# untitled.net
KiCad netlist of a schematic drawn in EAGLE
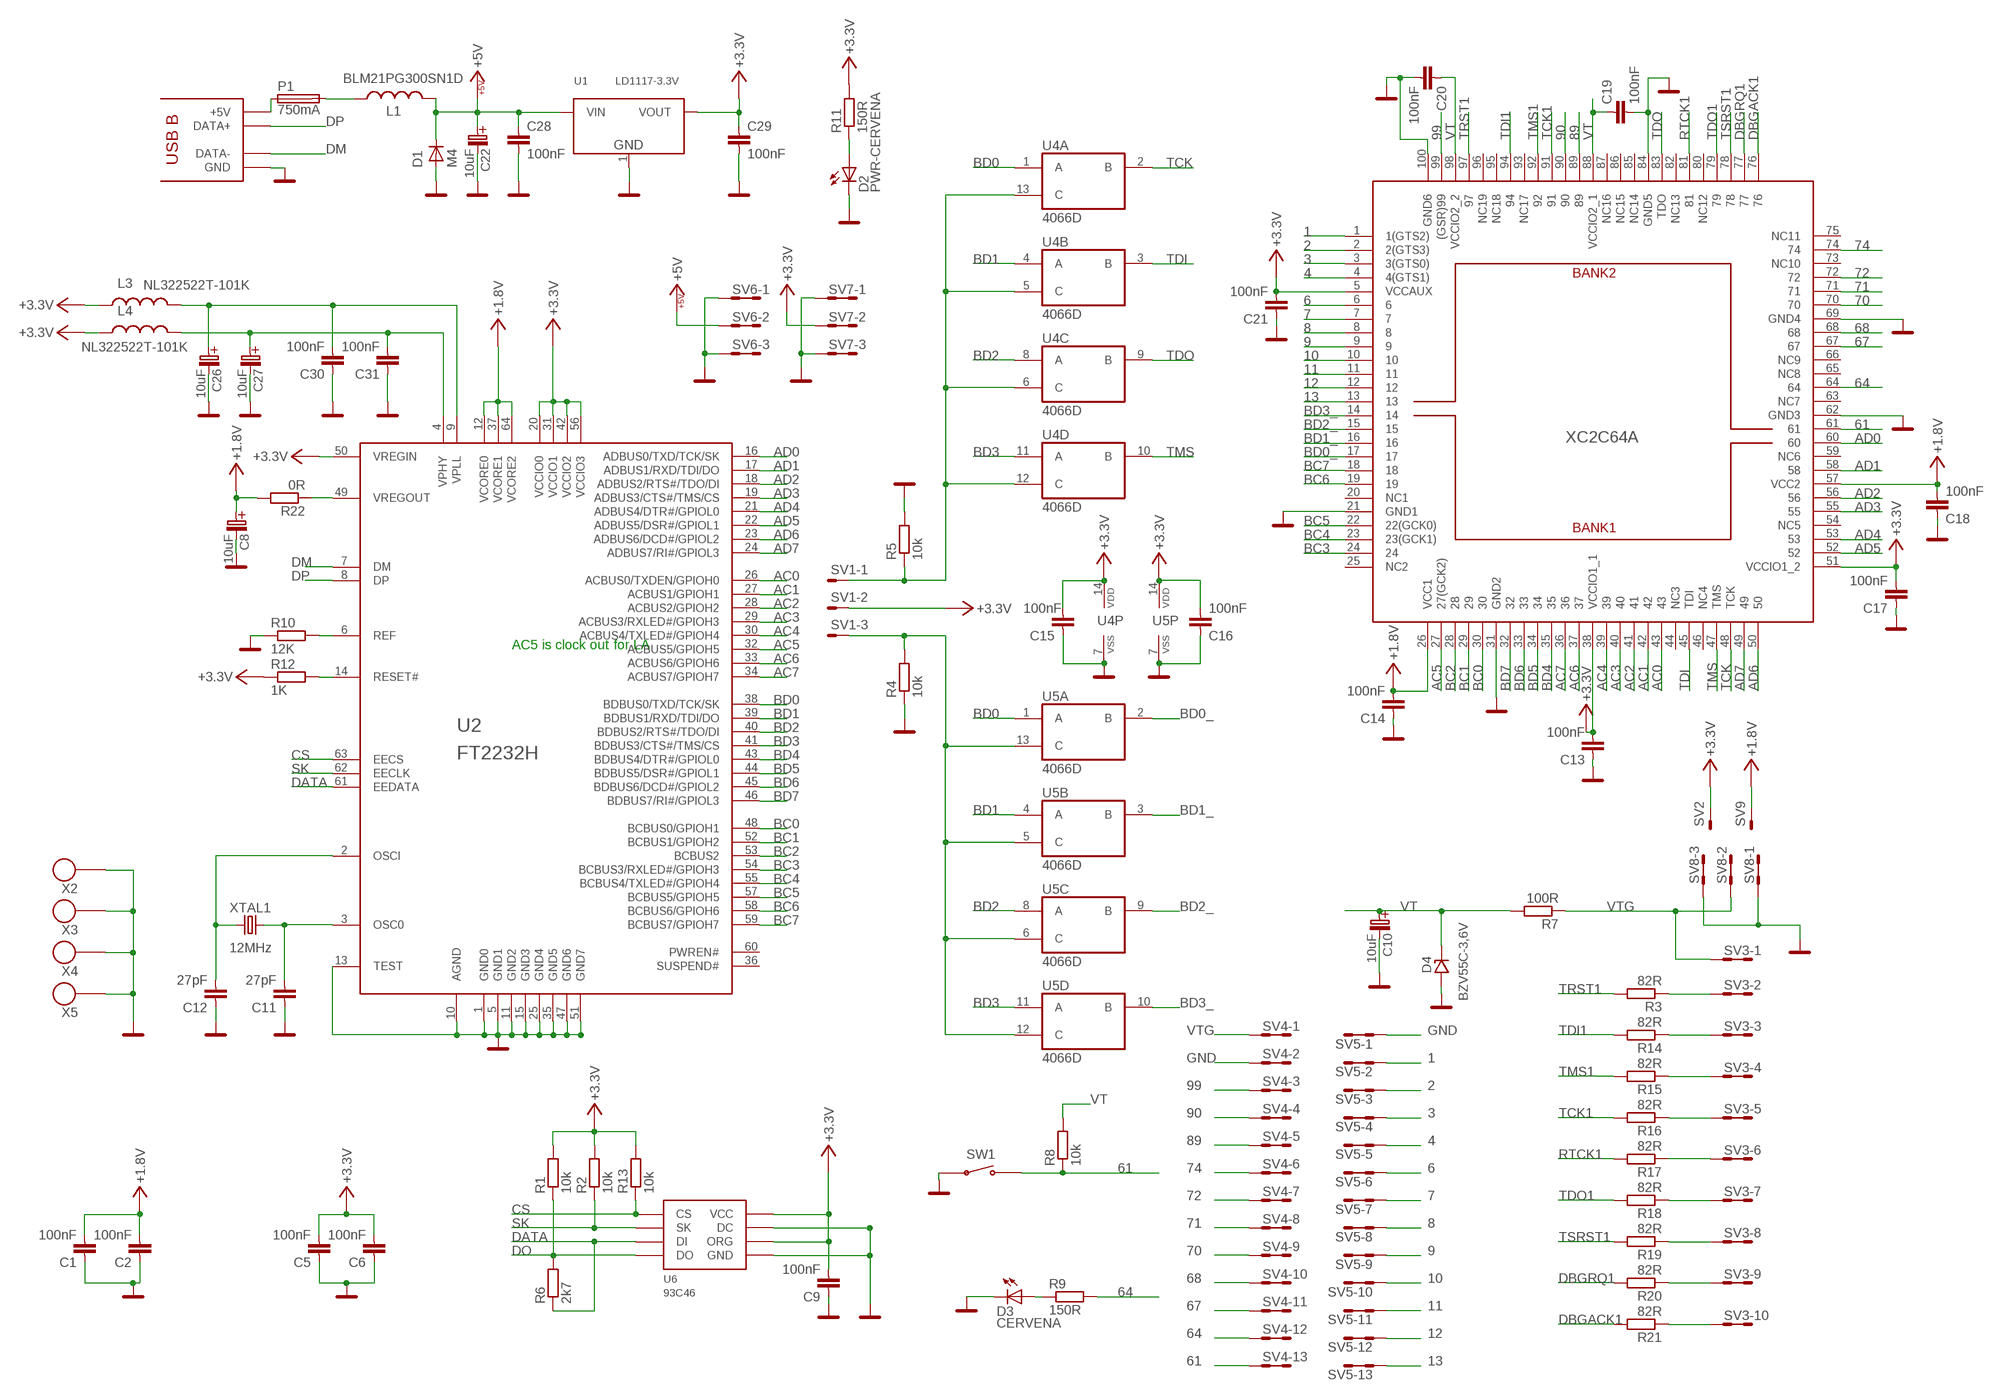
[diagram p0: schematic, sheet 1]

(export (version "E")
  (design (tool "Eeschema 10.0.6"))
  (components
    (comp (ref "C1")
      (value "100nF")
      (footprint "eagle-import:C0805")
      (libsource (lib "eagle-import") (part "C0805"))
    )
    (comp (ref "C2")
      (value "100nF")
      (footprint "eagle-import:C0805")
      (libsource (lib "eagle-import") (part "C0805"))
    )
    (comp (ref "C5")
      (value "100nF")
      (footprint "eagle-import:C0805")
      (libsource (lib "eagle-import") (part "C0805"))
    )
    (comp (ref "C6")
      (value "100nF")
      (footprint "eagle-import:C0805")
      (libsource (lib "eagle-import") (part "C0805"))
    )
    (comp (ref "C8") (value "10uF") (footprint "eagle-import:B") (libsource (lib "eagle-import") (part "B")))
    (comp (ref "C9")
      (value "100nF")
      (footprint "eagle-import:C0805")
      (libsource (lib "eagle-import") (part "C0805"))
    )
    (comp (ref "C10") (value "10uF") (footprint "eagle-import:B") (libsource (lib "eagle-import") (part "B")))
    (comp (ref "C11")
      (value "27pF")
      (footprint "eagle-import:C0805")
      (libsource (lib "eagle-import") (part "C0805"))
    )
    (comp (ref "C12")
      (value "27pF")
      (footprint "eagle-import:C0805")
      (libsource (lib "eagle-import") (part "C0805"))
    )
    (comp (ref "C13")
      (value "100nF")
      (footprint "eagle-import:C0805")
      (libsource (lib "eagle-import") (part "C0805"))
    )
    (comp (ref "C14")
      (value "100nF")
      (footprint "eagle-import:C0805")
      (libsource (lib "eagle-import") (part "C0805"))
    )
    (comp (ref "C15")
      (value "100nF")
      (footprint "eagle-import:C0805")
      (libsource (lib "eagle-import") (part "C0805"))
    )
    (comp (ref "C16")
      (value "100nF")
      (footprint "eagle-import:C0805")
      (libsource (lib "eagle-import") (part "C0805"))
    )
    (comp (ref "C17")
      (value "100nF")
      (footprint "eagle-import:C0805")
      (libsource (lib "eagle-import") (part "C0805"))
    )
    (comp (ref "C18")
      (value "100nF")
      (footprint "eagle-import:C0805")
      (libsource (lib "eagle-import") (part "C0805"))
    )
    (comp (ref "C19")
      (value "100nF")
      (footprint "eagle-import:C0805")
      (libsource (lib "eagle-import") (part "C0805"))
    )
    (comp (ref "C20")
      (value "100nF")
      (footprint "eagle-import:C0805")
      (libsource (lib "eagle-import") (part "C0805"))
    )
    (comp (ref "C21")
      (value "100nF")
      (footprint "eagle-import:C0805")
      (libsource (lib "eagle-import") (part "C0805"))
    )
    (comp (ref "C22") (value "10uF") (footprint "eagle-import:B") (libsource (lib "eagle-import") (part "B")))
    (comp (ref "C26") (value "10uF") (footprint "eagle-import:B") (libsource (lib "eagle-import") (part "B")))
    (comp (ref "C27") (value "10uF") (footprint "eagle-import:B") (libsource (lib "eagle-import") (part "B")))
    (comp (ref "C28")
      (value "100nF")
      (footprint "eagle-import:C0805")
      (libsource (lib "eagle-import") (part "C0805"))
    )
    (comp (ref "C29")
      (value "100nF")
      (footprint "eagle-import:C0805")
      (libsource (lib "eagle-import") (part "C0805"))
    )
    (comp (ref "C30")
      (value "100nF")
      (footprint "eagle-import:C0805")
      (libsource (lib "eagle-import") (part "C0805"))
    )
    (comp (ref "C31")
      (value "100nF")
      (footprint "eagle-import:C0805")
      (libsource (lib "eagle-import") (part "C0805"))
    )
    (comp (ref "D1")
      (value "M4")
      (footprint "eagle-import:SMA")
      (libsource (lib "eagle-import") (part "D-OB.SMA"))
    )
    (comp (ref "D2")
      (value "PWR-CERVENA")
      (footprint "eagle-import:1206")
      (libsource (lib "eagle-import") (part "LED1206"))
    )
    (comp (ref "D3")
      (value "CERVENA")
      (footprint "eagle-import:1206")
      (libsource (lib "eagle-import") (part "LED1206"))
    )
    (comp (ref "D4")
      (value "BZV55C-3,6V")
      (footprint "eagle-import:MINIMELF")
      (libsource (lib "eagle-import") (part "D-ZENEROVA"))
    )
    (comp (ref "L1")
      (value "BLM21PG300SN1D")
      (footprint "eagle-import:L0805")
      (libsource (lib "eagle-import") (part "L0805"))
    )
    (comp (ref "L3")
      (value "NL322522T-101K")
      (footprint "eagle-import:1210")
      (libsource (lib "eagle-import") (part "L1210"))
    )
    (comp (ref "L4")
      (value "NL322522T-101K")
      (footprint "eagle-import:1210")
      (libsource (lib "eagle-import") (part "L1210"))
    )
    (comp (ref "P1")
      (value "750mA")
      (footprint "eagle-import:1812")
      (libsource (lib "eagle-import") (part "POJISTKA_1812"))
    )
    (comp (ref "R1")
      (value "10k")
      (footprint "eagle-import:0805")
      (libsource (lib "eagle-import") (part "R0805"))
    )
    (comp (ref "R2")
      (value "10k")
      (footprint "eagle-import:0805")
      (libsource (lib "eagle-import") (part "R0805"))
    )
    (comp (ref "R3")
      (value "82R")
      (footprint "eagle-import:0805")
      (libsource (lib "eagle-import") (part "R0805"))
    )
    (comp (ref "R4")
      (value "10k")
      (footprint "eagle-import:0805")
      (libsource (lib "eagle-import") (part "R0805"))
    )
    (comp (ref "R5")
      (value "10k")
      (footprint "eagle-import:0805")
      (libsource (lib "eagle-import") (part "R0805"))
    )
    (comp (ref "R6")
      (value "2k7")
      (footprint "eagle-import:0805")
      (libsource (lib "eagle-import") (part "R0805"))
    )
    (comp (ref "R7")
      (value "100R")
      (footprint "eagle-import:0805")
      (libsource (lib "eagle-import") (part "R0805"))
    )
    (comp (ref "R8")
      (value "10k")
      (footprint "eagle-import:0805")
      (libsource (lib "eagle-import") (part "R0805"))
    )
    (comp (ref "R9")
      (value "150R")
      (footprint "eagle-import:0805")
      (libsource (lib "eagle-import") (part "R0805"))
    )
    (comp (ref "R10")
      (value "12K")
      (footprint "eagle-import:0805")
      (libsource (lib "eagle-import") (part "R0805"))
    )
    (comp (ref "R11")
      (value "150R")
      (footprint "eagle-import:0805")
      (libsource (lib "eagle-import") (part "R0805"))
    )
    (comp (ref "R12")
      (value "1K")
      (footprint "eagle-import:0805")
      (libsource (lib "eagle-import") (part "R0805"))
    )
    (comp (ref "R13")
      (value "10k")
      (footprint "eagle-import:0805")
      (libsource (lib "eagle-import") (part "R0805"))
    )
    (comp (ref "R14")
      (value "82R")
      (footprint "eagle-import:0805")
      (libsource (lib "eagle-import") (part "R0805"))
    )
    (comp (ref "R15")
      (value "82R")
      (footprint "eagle-import:0805")
      (libsource (lib "eagle-import") (part "R0805"))
    )
    (comp (ref "R16")
      (value "82R")
      (footprint "eagle-import:0805")
      (libsource (lib "eagle-import") (part "R0805"))
    )
    (comp (ref "R17")
      (value "82R")
      (footprint "eagle-import:0805")
      (libsource (lib "eagle-import") (part "R0805"))
    )
    (comp (ref "R18")
      (value "82R")
      (footprint "eagle-import:0805")
      (libsource (lib "eagle-import") (part "R0805"))
    )
    (comp (ref "R19")
      (value "82R")
      (footprint "eagle-import:0805")
      (libsource (lib "eagle-import") (part "R0805"))
    )
    (comp (ref "R20")
      (value "82R")
      (footprint "eagle-import:0805")
      (libsource (lib "eagle-import") (part "R0805"))
    )
    (comp (ref "R21")
      (value "82R")
      (footprint "eagle-import:0805")
      (libsource (lib "eagle-import") (part "R0805"))
    )
    (comp (ref "R22")
      (value "0R")
      (footprint "eagle-import:0805")
      (libsource (lib "eagle-import") (part "R0805"))
    )
    (comp (ref "SV1")
      (value "MA03-1")
      (footprint "eagle-import:MA03-1")
      (libsource (lib "eagle-import") (part "MA03-1"))
    )
    (comp (ref "SV2")
      (value "MA01-1")
      (footprint "eagle-import:MA01-1")
      (libsource (lib "eagle-import") (part "MA01-1"))
    )
    (comp (ref "SV3")
      (value "MA10-2")
      (footprint "eagle-import:MA10-2")
      (libsource (lib "eagle-import") (part "MA10-2"))
    )
    (comp (ref "SV4")
      (value "MA13-2")
      (footprint "eagle-import:MA13-2")
      (libsource (lib "eagle-import") (part "MA13-2"))
    )
    (comp (ref "SV5")
      (value "MA13-2")
      (footprint "eagle-import:MA13-2")
      (libsource (lib "eagle-import") (part "MA13-2"))
    )
    (comp (ref "SV6")
      (value "MA03-2")
      (footprint "eagle-import:MA03-2")
      (libsource (lib "eagle-import") (part "MA03-2"))
    )
    (comp (ref "SV7")
      (value "MA03-2")
      (footprint "eagle-import:MA03-2")
      (libsource (lib "eagle-import") (part "MA03-2"))
    )
    (comp (ref "SV8")
      (value "MA03-2")
      (footprint "eagle-import:MA03-2")
      (libsource (lib "eagle-import") (part "MA03-2"))
    )
    (comp (ref "SV9")
      (value "MA01-1")
      (footprint "eagle-import:MA01-1")
      (libsource (lib "eagle-import") (part "MA01-1"))
    )
    (comp (ref "SW1")
      (value "TACT-64K")
      (footprint "eagle-import:TACT-64K")
      (libsource (lib "eagle-import") (part "TACT-64K"))
    )
    (comp (ref "U1")
      (value "LD1117-3.3V")
      (footprint "eagle-import:SOT223")
      (libsource (lib "eagle-import") (part "LD1117-3.3SOT223"))
    )
    (comp (ref "U2")
      (value "FT2232H")
      (footprint "eagle-import:LQFP64")
      (libsource (lib "eagle-import") (part "FT2232H"))
    )
    (comp (ref "U3")
      (value "XC2C64A")
      (footprint "eagle-import:VQ100")
      (libsource (lib "eagle-import") (part "XC2C64A"))
    )
    (comp (ref "U4")
      (value "4066D")
      (footprint "eagle-import:SO14")
      (libsource (lib "eagle-import") (part "4066D"))
    )
    (comp (ref "U5")
      (value "4066D")
      (footprint "eagle-import:SO14")
      (libsource (lib "eagle-import") (part "4066D"))
    )
    (comp (ref "U6")
      (value "93C46")
      (footprint "eagle-import:SOIC8")
      (libsource (lib "eagle-import") (part "93C46"))
    )
    (comp (ref "X1")
      (value "USB_B")
      (footprint "eagle-import:USB_B")
      (libsource (lib "eagle-import") (part "USB_B"))
    )
    (comp (ref "X2")
      (value "SROUB3M")
      (footprint "eagle-import:SROUB3M")
      (libsource (lib "eagle-import") (part "SROUB3M"))
    )
    (comp (ref "X3")
      (value "SROUB3M")
      (footprint "eagle-import:SROUB3M")
      (libsource (lib "eagle-import") (part "SROUB3M"))
    )
    (comp (ref "X4")
      (value "SROUB3M")
      (footprint "eagle-import:SROUB3M")
      (libsource (lib "eagle-import") (part "SROUB3M"))
    )
    (comp (ref "X5")
      (value "SROUB3M")
      (footprint "eagle-import:SROUB3M")
      (libsource (lib "eagle-import") (part "SROUB3M"))
    )
    (comp (ref "XTAL1")
      (value "12MHz")
      (footprint "eagle-import:S49")
      (libsource (lib "eagle-import") (part "KRYSLAL_S49"))
    )
  )
  (nets
    (net (code "1") (name "+1.8V") (class "Default")
      (node (ref "C1") (pin "2") (pinfunction "2_2") (pintype "passive"))
      (node (ref "C14") (pin "2") (pinfunction "2_2") (pintype "passive"))
      (node (ref "C18") (pin "2") (pinfunction "2_2") (pintype "passive"))
      (node (ref "C2") (pin "2") (pinfunction "2_2") (pintype "passive"))
      (node (ref "C8") (pin "+") (pinfunction "C_EL+_+") (pintype "passive"))
      (node (ref "R22") (pin "2") (pinfunction "2_2") (pintype "passive"))
      (node (ref "SV9") (pin "1") (pinfunction "P$1_1") (pintype "passive"))
      (node (ref "U2") (pin "12") (pinfunction "VCORE0_12") (pintype "bidirectional"))
      (node (ref "U2") (pin "37") (pinfunction "VCORE1_37") (pintype "bidirectional"))
      (node (ref "U2") (pin "64") (pinfunction "VCORE2_64") (pintype "bidirectional"))
      (node (ref "U3") (pin "26") (pinfunction "VCC1_26") (pintype "bidirectional"))
      (node (ref "U3") (pin "57") (pinfunction "VCC2_57") (pintype "bidirectional"))
    )
    (net (code "2") (name "+3.3V") (class "Default")
      (node (ref "C13") (pin "2") (pinfunction "2_2") (pintype "passive"))
      (node (ref "C15") (pin "2") (pinfunction "2_2") (pintype "passive"))
      (node (ref "C16") (pin "2") (pinfunction "2_2") (pintype "passive"))
      (node (ref "C17") (pin "2") (pinfunction "2_2") (pintype "passive"))
      (node (ref "C21") (pin "2") (pinfunction "2_2") (pintype "passive"))
      (node (ref "C29") (pin "1") (pinfunction "1_1") (pintype "passive"))
      (node (ref "C5") (pin "2") (pinfunction "2_2") (pintype "passive"))
      (node (ref "C6") (pin "2") (pinfunction "2_2") (pintype "passive"))
      (node (ref "C9") (pin "2") (pinfunction "2_2") (pintype "passive"))
      (node (ref "L3") (pin "P$1") (pinfunction "1_P$1") (pintype "passive"))
      (node (ref "L4") (pin "P$1") (pinfunction "1_P$1") (pintype "passive"))
      (node (ref "R1") (pin "2") (pinfunction "2_2") (pintype "passive"))
      (node (ref "R11") (pin "2") (pinfunction "2_2") (pintype "passive"))
      (node (ref "R12") (pin "1") (pinfunction "1_1") (pintype "passive"))
      (node (ref "R13") (pin "2") (pinfunction "2_2") (pintype "passive"))
      (node (ref "R2") (pin "2") (pinfunction "2_2") (pintype "passive"))
      (node (ref "SV1") (pin "2") (pinfunction "P$1_2") (pintype "passive"))
      (node (ref "SV2") (pin "1") (pinfunction "P$1_1") (pintype "passive"))
      (node (ref "SV7") (pin "3") (pinfunction "K_3") (pintype "passive"))
      (node (ref "SV7") (pin "4") (pinfunction "K_4") (pintype "passive"))
      (node (ref "U1") (pin "2") (pinfunction "VOUT_2") (pintype "bidirectional"))
      (node (ref "U2") (pin "20") (pinfunction "VCCIO0_20") (pintype "bidirectional"))
      (node (ref "U2") (pin "31") (pinfunction "VCCIO1_31") (pintype "bidirectional"))
      (node (ref "U2") (pin "42") (pinfunction "VCCIO2_42") (pintype "bidirectional"))
      (node (ref "U2") (pin "50") (pinfunction "VREGIN_50") (pintype "bidirectional"))
      (node (ref "U2") (pin "56") (pinfunction "VCCIO3_56") (pintype "bidirectional"))
      (node (ref "U3") (pin "38") (pinfunction "VCCIO1_1_38") (pintype "bidirectional"))
      (node (ref "U3") (pin "5") (pinfunction "VCCAUX_5") (pintype "bidirectional"))
      (node (ref "U3") (pin "51") (pinfunction "VCCIO1_2_51") (pintype "bidirectional"))
      (node (ref "U4") (pin "14") (pinfunction "VDD_14") (pintype "power_in"))
      (node (ref "U5") (pin "14") (pinfunction "VDD_14") (pintype "power_in"))
      (node (ref "U6") (pin "6") (pinfunction "ORG_6") (pintype "bidirectional"))
      (node (ref "U6") (pin "8") (pinfunction "VCC_8") (pintype "bidirectional"))
    )
    (net (code "3") (name "+5V") (class "Default")
      (node (ref "C22") (pin "+") (pinfunction "C_EL+_+") (pintype "passive"))
      (node (ref "C28") (pin "1") (pinfunction "1_1") (pintype "passive"))
      (node (ref "D1") (pin "K") (pinfunction "C_K") (pintype "passive"))
      (node (ref "L1") (pin "2") (pinfunction "2_2") (pintype "passive"))
      (node (ref "SV6") (pin "3") (pinfunction "K_3") (pintype "passive"))
      (node (ref "SV6") (pin "4") (pinfunction "K_4") (pintype "passive"))
      (node (ref "U1") (pin "3") (pinfunction "VIN_3") (pintype "bidirectional"))
    )
    (net (code "4") (name "/1") (class "Default")
      (node (ref "SV5") (pin "3") (pinfunction "K_3") (pintype "passive"))
      (node (ref "SV5") (pin "4") (pinfunction "K_4") (pintype "passive"))
      (node (ref "U3") (pin "1") (pinfunction "1(GTS2)_1") (pintype "bidirectional"))
    )
    (net (code "5") (name "/2") (class "Default")
      (node (ref "SV5") (pin "5") (pinfunction "K_5") (pintype "passive"))
      (node (ref "SV5") (pin "6") (pinfunction "K_6") (pintype "passive"))
      (node (ref "U3") (pin "2") (pinfunction "2(GTS3)_2") (pintype "bidirectional"))
    )
    (net (code "6") (name "/3") (class "Default")
      (node (ref "SV5") (pin "7") (pinfunction "K_7") (pintype "passive"))
      (node (ref "SV5") (pin "8") (pinfunction "K_8") (pintype "passive"))
      (node (ref "U3") (pin "3") (pinfunction "3(GTS0)_3") (pintype "bidirectional"))
    )
    (net (code "7") (name "/4") (class "Default")
      (node (ref "SV5") (pin "10") (pinfunction "K_10") (pintype "passive"))
      (node (ref "SV5") (pin "9") (pinfunction "K_9") (pintype "passive"))
      (node (ref "U3") (pin "4") (pinfunction "4(GTS1)_4") (pintype "bidirectional"))
    )
    (net (code "8") (name "/6") (class "Default")
      (node (ref "SV5") (pin "11") (pinfunction "K_11") (pintype "passive"))
      (node (ref "SV5") (pin "12") (pinfunction "K_12") (pintype "passive"))
      (node (ref "U3") (pin "6") (pinfunction "6_6") (pintype "bidirectional"))
    )
    (net (code "9") (name "/7") (class "Default")
      (node (ref "SV5") (pin "13") (pinfunction "K_13") (pintype "passive"))
      (node (ref "SV5") (pin "14") (pinfunction "K_14") (pintype "passive"))
      (node (ref "U3") (pin "7") (pinfunction "7_7") (pintype "bidirectional"))
    )
    (net (code "10") (name "/8") (class "Default")
      (node (ref "SV5") (pin "15") (pinfunction "K_15") (pintype "passive"))
      (node (ref "SV5") (pin "16") (pinfunction "K_16") (pintype "passive"))
      (node (ref "U3") (pin "8") (pinfunction "8_8") (pintype "bidirectional"))
    )
    (net (code "11") (name "/9") (class "Default")
      (node (ref "SV5") (pin "17") (pinfunction "K_17") (pintype "passive"))
      (node (ref "SV5") (pin "18") (pinfunction "K_18") (pintype "passive"))
      (node (ref "U3") (pin "9") (pinfunction "9_9") (pintype "bidirectional"))
    )
    (net (code "12") (name "/10") (class "Default")
      (node (ref "SV5") (pin "19") (pinfunction "K_19") (pintype "passive"))
      (node (ref "SV5") (pin "20") (pinfunction "K_20") (pintype "passive"))
      (node (ref "U3") (pin "10") (pinfunction "10_10") (pintype "bidirectional"))
    )
    (net (code "13") (name "/11") (class "Default")
      (node (ref "SV5") (pin "21") (pinfunction "K_21") (pintype "passive"))
      (node (ref "SV5") (pin "22") (pinfunction "K_22") (pintype "passive"))
      (node (ref "U3") (pin "11") (pinfunction "11_11") (pintype "bidirectional"))
    )
    (net (code "14") (name "/12") (class "Default")
      (node (ref "SV5") (pin "23") (pinfunction "K_23") (pintype "passive"))
      (node (ref "SV5") (pin "24") (pinfunction "K_24") (pintype "passive"))
      (node (ref "U3") (pin "12") (pinfunction "12_12") (pintype "bidirectional"))
    )
    (net (code "15") (name "/13") (class "Default")
      (node (ref "SV5") (pin "25") (pinfunction "K_25") (pintype "passive"))
      (node (ref "SV5") (pin "26") (pinfunction "K_26") (pintype "passive"))
      (node (ref "U3") (pin "13") (pinfunction "13_13") (pintype "bidirectional"))
    )
    (net (code "16") (name "/61") (class "Default")
      (node (ref "R8") (pin "1") (pinfunction "1_1") (pintype "passive"))
      (node (ref "SV4") (pin "25") (pinfunction "K_25") (pintype "passive"))
      (node (ref "SV4") (pin "26") (pinfunction "K_26") (pintype "passive"))
      (node (ref "SW1") (pin "P$3") (pinfunction "P$2_P$3") (pintype "passive"))
      (node (ref "SW1") (pin "P$4") (pinfunction "P$2_P$4") (pintype "passive"))
      (node (ref "U3") (pin "61") (pinfunction "61_61") (pintype "bidirectional"))
    )
    (net (code "17") (name "/64") (class "Default")
      (node (ref "R9") (pin "2") (pinfunction "2_2") (pintype "passive"))
      (node (ref "SV4") (pin "23") (pinfunction "K_23") (pintype "passive"))
      (node (ref "SV4") (pin "24") (pinfunction "K_24") (pintype "passive"))
      (node (ref "U3") (pin "64") (pinfunction "64_64") (pintype "bidirectional"))
    )
    (net (code "18") (name "/67") (class "Default")
      (node (ref "SV4") (pin "21") (pinfunction "K_21") (pintype "passive"))
      (node (ref "SV4") (pin "22") (pinfunction "K_22") (pintype "passive"))
      (node (ref "U3") (pin "67") (pinfunction "67_67") (pintype "bidirectional"))
    )
    (net (code "19") (name "/68") (class "Default")
      (node (ref "SV4") (pin "19") (pinfunction "K_19") (pintype "passive"))
      (node (ref "SV4") (pin "20") (pinfunction "K_20") (pintype "passive"))
      (node (ref "U3") (pin "68") (pinfunction "68_68") (pintype "bidirectional"))
    )
    (net (code "20") (name "/70") (class "Default")
      (node (ref "SV4") (pin "17") (pinfunction "K_17") (pintype "passive"))
      (node (ref "SV4") (pin "18") (pinfunction "K_18") (pintype "passive"))
      (node (ref "U3") (pin "70") (pinfunction "70_70") (pintype "bidirectional"))
    )
    (net (code "21") (name "/71") (class "Default")
      (node (ref "SV4") (pin "15") (pinfunction "K_15") (pintype "passive"))
      (node (ref "SV4") (pin "16") (pinfunction "K_16") (pintype "passive"))
      (node (ref "U3") (pin "71") (pinfunction "71_71") (pintype "bidirectional"))
    )
    (net (code "22") (name "/72") (class "Default")
      (node (ref "SV4") (pin "13") (pinfunction "K_13") (pintype "passive"))
      (node (ref "SV4") (pin "14") (pinfunction "K_14") (pintype "passive"))
      (node (ref "U3") (pin "72") (pinfunction "72_72") (pintype "bidirectional"))
    )
    (net (code "23") (name "/74") (class "Default")
      (node (ref "SV4") (pin "11") (pinfunction "K_11") (pintype "passive"))
      (node (ref "SV4") (pin "12") (pinfunction "K_12") (pintype "passive"))
      (node (ref "U3") (pin "74") (pinfunction "74_74") (pintype "bidirectional"))
    )
    (net (code "24") (name "/89") (class "Default")
      (node (ref "SV4") (pin "10") (pinfunction "K_10") (pintype "passive"))
      (node (ref "SV4") (pin "9") (pinfunction "K_9") (pintype "passive"))
      (node (ref "U3") (pin "89") (pinfunction "89_89") (pintype "bidirectional"))
    )
    (net (code "25") (name "/90") (class "Default")
      (node (ref "SV4") (pin "7") (pinfunction "K_7") (pintype "passive"))
      (node (ref "SV4") (pin "8") (pinfunction "K_8") (pintype "passive"))
      (node (ref "U3") (pin "90") (pinfunction "90_90") (pintype "bidirectional"))
    )
    (net (code "26") (name "/99") (class "Default")
      (node (ref "SV4") (pin "5") (pinfunction "K_5") (pintype "passive"))
      (node (ref "SV4") (pin "6") (pinfunction "K_6") (pintype "passive"))
      (node (ref "U3") (pin "99") (pinfunction "(GSR)99_99") (pintype "bidirectional"))
    )
    (net (code "27") (name "/AC0") (class "Default")
      (node (ref "U2") (pin "26") (pinfunction "ACBUS0/TXDEN/GPIOH0_26") (pintype "bidirectional"))
      (node (ref "U3") (pin "43") (pinfunction "43_43") (pintype "bidirectional"))
    )
    (net (code "28") (name "/AC1") (class "Default")
      (node (ref "U2") (pin "27") (pinfunction "ACBUS1/GPIOH1_27") (pintype "bidirectional"))
      (node (ref "U3") (pin "42") (pinfunction "42_42") (pintype "bidirectional"))
    )
    (net (code "29") (name "/AC2") (class "Default")
      (node (ref "U2") (pin "28") (pinfunction "ACBUS2/GPIOH2_28") (pintype "bidirectional"))
      (node (ref "U3") (pin "41") (pinfunction "41_41") (pintype "bidirectional"))
    )
    (net (code "30") (name "/AC3") (class "Default")
      (node (ref "U2") (pin "29") (pinfunction "ACBUS3/RXLED#/GPIOH3_29") (pintype "bidirectional"))
      (node (ref "U3") (pin "40") (pinfunction "40_40") (pintype "bidirectional"))
    )
    (net (code "31") (name "/AC4") (class "Default")
      (node (ref "U2") (pin "30") (pinfunction "ACBUS4/TXLED#/GPIOH4_30") (pintype "bidirectional"))
      (node (ref "U3") (pin "39") (pinfunction "39_39") (pintype "bidirectional"))
    )
    (net (code "32") (name "/AC5") (class "Default")
      (node (ref "U2") (pin "32") (pinfunction "ACBUS5/GPIOH5_32") (pintype "bidirectional"))
      (node (ref "U3") (pin "27") (pinfunction "27(GCK2)_27") (pintype "bidirectional"))
    )
    (net (code "33") (name "/AC6") (class "Default")
      (node (ref "U2") (pin "33") (pinfunction "ACBUS6/GPIOH6_33") (pintype "bidirectional"))
      (node (ref "U3") (pin "37") (pinfunction "37_37") (pintype "bidirectional"))
    )
    (net (code "34") (name "/AC7") (class "Default")
      (node (ref "U2") (pin "34") (pinfunction "ACBUS7/GPIOH7_34") (pintype "bidirectional"))
      (node (ref "U3") (pin "36") (pinfunction "36_36") (pintype "bidirectional"))
    )
    (net (code "35") (name "/AD0") (class "Default")
      (node (ref "U2") (pin "16") (pinfunction "ADBUS0/TXD/TCK/SK_16") (pintype "bidirectional"))
      (node (ref "U3") (pin "60") (pinfunction "60_60") (pintype "bidirectional"))
    )
    (net (code "36") (name "/AD1") (class "Default")
      (node (ref "U2") (pin "17") (pinfunction "ADBUS1/RXD/TDI/DO_17") (pintype "bidirectional"))
      (node (ref "U3") (pin "58") (pinfunction "58_58") (pintype "bidirectional"))
    )
    (net (code "37") (name "/AD2") (class "Default")
      (node (ref "U2") (pin "18") (pinfunction "ADBUS2/RTS#/TDO/DI_18") (pintype "bidirectional"))
      (node (ref "U3") (pin "56") (pinfunction "56_56") (pintype "bidirectional"))
    )
    (net (code "38") (name "/AD3") (class "Default")
      (node (ref "U2") (pin "19") (pinfunction "ADBUS3/CTS#/TMS/CS_19") (pintype "bidirectional"))
      (node (ref "U3") (pin "55") (pinfunction "55_55") (pintype "bidirectional"))
    )
    (net (code "39") (name "/AD4") (class "Default")
      (node (ref "U2") (pin "21") (pinfunction "ADBUS4/DTR#/GPIOL0_21") (pintype "bidirectional"))
      (node (ref "U3") (pin "53") (pinfunction "53_53") (pintype "bidirectional"))
    )
    (net (code "40") (name "/AD5") (class "Default")
      (node (ref "U2") (pin "22") (pinfunction "ADBUS5/DSR#/GPIOL1_22") (pintype "bidirectional"))
      (node (ref "U3") (pin "52") (pinfunction "52_52") (pintype "bidirectional"))
    )
    (net (code "41") (name "/AD6") (class "Default")
      (node (ref "U2") (pin "23") (pinfunction "ADBUS6/DCD#/GPIOL2_23") (pintype "bidirectional"))
      (node (ref "U3") (pin "50") (pinfunction "50_50") (pintype "bidirectional"))
    )
    (net (code "42") (name "/AD7") (class "Default")
      (node (ref "U2") (pin "24") (pinfunction "ADBUS7/RI#/GPIOL3_24") (pintype "bidirectional"))
      (node (ref "U3") (pin "49") (pinfunction "49_49") (pintype "bidirectional"))
    )
    (net (code "43") (name "/BC0") (class "Default")
      (node (ref "U2") (pin "48") (pinfunction "BCBUS0/GPIOH1_48") (pintype "bidirectional"))
      (node (ref "U3") (pin "30") (pinfunction "30_30") (pintype "bidirectional"))
    )
    (net (code "44") (name "/BC1") (class "Default")
      (node (ref "U2") (pin "52") (pinfunction "BCBUS1/GPIOH2_52") (pintype "bidirectional"))
      (node (ref "U3") (pin "29") (pinfunction "29_29") (pintype "bidirectional"))
    )
    (net (code "45") (name "/BC2") (class "Default")
      (node (ref "U2") (pin "53") (pinfunction "BCBUS2_53") (pintype "bidirectional"))
      (node (ref "U3") (pin "28") (pinfunction "28_28") (pintype "bidirectional"))
    )
    (net (code "46") (name "/BC3") (class "Default")
      (node (ref "U2") (pin "54") (pinfunction "BCBUS3/RXLED#/GPIOH3_54") (pintype "bidirectional"))
      (node (ref "U3") (pin "24") (pinfunction "24_24") (pintype "bidirectional"))
    )
    (net (code "47") (name "/BC4") (class "Default")
      (node (ref "U2") (pin "55") (pinfunction "BCBUS4/TXLED#/GPIOH4_55") (pintype "bidirectional"))
      (node (ref "U3") (pin "23") (pinfunction "23(GCK1)_23") (pintype "bidirectional"))
    )
    (net (code "48") (name "/BC5") (class "Default")
      (node (ref "U2") (pin "57") (pinfunction "BCBUS5/GPIOH5_57") (pintype "bidirectional"))
      (node (ref "U3") (pin "22") (pinfunction "22(GCK0)_22") (pintype "bidirectional"))
    )
    (net (code "49") (name "/BC6") (class "Default")
      (node (ref "U2") (pin "58") (pinfunction "BCBUS6/GPIOH6_58") (pintype "bidirectional"))
      (node (ref "U3") (pin "19") (pinfunction "19_19") (pintype "bidirectional"))
    )
    (net (code "50") (name "/BC7") (class "Default")
      (node (ref "U2") (pin "59") (pinfunction "BCBUS7/GPIOH7_59") (pintype "bidirectional"))
      (node (ref "U3") (pin "18") (pinfunction "18_18") (pintype "bidirectional"))
    )
    (net (code "51") (name "/BD0") (class "Default")
      (node (ref "U2") (pin "38") (pinfunction "BDBUS0/TXD/TCK/SK_38") (pintype "bidirectional"))
      (node (ref "U4") (pin "1") (pinfunction "A_1") (pintype "tri_state"))
      (node (ref "U5") (pin "1") (pinfunction "A_1") (pintype "tri_state"))
    )
    (net (code "52") (name "/BD0_") (class "Default")
      (node (ref "U3") (pin "17") (pinfunction "17_17") (pintype "bidirectional"))
      (node (ref "U5") (pin "2") (pinfunction "B_2") (pintype "tri_state"))
    )
    (net (code "53") (name "/BD1") (class "Default")
      (node (ref "U2") (pin "39") (pinfunction "BDBUS1/RXD/TDI/DO_39") (pintype "bidirectional"))
      (node (ref "U4") (pin "4") (pinfunction "A_4") (pintype "tri_state"))
      (node (ref "U5") (pin "4") (pinfunction "A_4") (pintype "tri_state"))
    )
    (net (code "54") (name "/BD1_") (class "Default")
      (node (ref "U3") (pin "16") (pinfunction "16_16") (pintype "bidirectional"))
      (node (ref "U5") (pin "3") (pinfunction "B_3") (pintype "tri_state"))
    )
    (net (code "55") (name "/BD2") (class "Default")
      (node (ref "U2") (pin "40") (pinfunction "BDBUS2/RTS#/TDO/DI_40") (pintype "bidirectional"))
      (node (ref "U4") (pin "8") (pinfunction "A_8") (pintype "tri_state"))
      (node (ref "U5") (pin "8") (pinfunction "A_8") (pintype "tri_state"))
    )
    (net (code "56") (name "/BD2_") (class "Default")
      (node (ref "U3") (pin "15") (pinfunction "15_15") (pintype "bidirectional"))
      (node (ref "U5") (pin "9") (pinfunction "B_9") (pintype "tri_state"))
    )
    (net (code "57") (name "/BD3") (class "Default")
      (node (ref "U2") (pin "41") (pinfunction "BDBUS3/CTS#/TMS/CS_41") (pintype "bidirectional"))
      (node (ref "U4") (pin "11") (pinfunction "A_11") (pintype "tri_state"))
      (node (ref "U5") (pin "11") (pinfunction "A_11") (pintype "tri_state"))
    )
    (net (code "58") (name "/BD3_") (class "Default")
      (node (ref "U3") (pin "14") (pinfunction "14_14") (pintype "bidirectional"))
      (node (ref "U5") (pin "10") (pinfunction "B_10") (pintype "tri_state"))
    )
    (net (code "59") (name "/BD4") (class "Default")
      (node (ref "U2") (pin "43") (pinfunction "BDBUS4/DTR#/GPIOL0_43") (pintype "bidirectional"))
      (node (ref "U3") (pin "35") (pinfunction "35_35") (pintype "bidirectional"))
    )
    (net (code "60") (name "/BD5") (class "Default")
      (node (ref "U2") (pin "44") (pinfunction "BDBUS5/DSR#/GPIOL1_44") (pintype "bidirectional"))
      (node (ref "U3") (pin "34") (pinfunction "34_34") (pintype "bidirectional"))
    )
    (net (code "61") (name "/BD6") (class "Default")
      (node (ref "U2") (pin "45") (pinfunction "BDBUS6/DCD#/GPIOL2_45") (pintype "bidirectional"))
      (node (ref "U3") (pin "33") (pinfunction "33_33") (pintype "bidirectional"))
    )
    (net (code "62") (name "/BD7") (class "Default")
      (node (ref "U2") (pin "46") (pinfunction "BDBUS7/RI#/GPIOL3_46") (pintype "bidirectional"))
      (node (ref "U3") (pin "32") (pinfunction "32_32") (pintype "bidirectional"))
    )
    (net (code "63") (name "/CS") (class "Default")
      (node (ref "R13") (pin "1") (pinfunction "1_1") (pintype "passive"))
      (node (ref "U2") (pin "63") (pinfunction "EECS_63") (pintype "bidirectional"))
      (node (ref "U6") (pin "1") (pinfunction "CS_1") (pintype "bidirectional"))
    )
    (net (code "64") (name "/DATA") (class "Default")
      (node (ref "R6") (pin "1") (pinfunction "1_1") (pintype "passive"))
      (node (ref "U2") (pin "61") (pinfunction "EEDATA_61") (pintype "bidirectional"))
      (node (ref "U6") (pin "3") (pinfunction "DI_3") (pintype "bidirectional"))
    )
    (net (code "65") (name "/DBGACK1") (class "Default")
      (node (ref "R21") (pin "2") (pinfunction "2_2") (pintype "passive"))
      (node (ref "U3") (pin "76") (pinfunction "76_76") (pintype "bidirectional"))
    )
    (net (code "66") (name "/DBGRQ1") (class "Default")
      (node (ref "R20") (pin "2") (pinfunction "2_2") (pintype "passive"))
      (node (ref "U3") (pin "77") (pinfunction "77_77") (pintype "bidirectional"))
    )
    (net (code "67") (name "/DM") (class "Default")
      (node (ref "U2") (pin "7") (pinfunction "DM_7") (pintype "bidirectional"))
      (node (ref "X1") (pin "2") (pinfunction "DATA-_2") (pintype "bidirectional"))
    )
    (net (code "68") (name "/DO") (class "Default")
      (node (ref "R1") (pin "1") (pinfunction "1_1") (pintype "passive"))
      (node (ref "R6") (pin "2") (pinfunction "2_2") (pintype "passive"))
      (node (ref "U6") (pin "4") (pinfunction "DO_4") (pintype "bidirectional"))
    )
    (net (code "69") (name "/DP") (class "Default")
      (node (ref "U2") (pin "8") (pinfunction "DP_8") (pintype "bidirectional"))
      (node (ref "X1") (pin "3") (pinfunction "DATA+_3") (pintype "bidirectional"))
    )
    (net (code "70") (name "/RTCK1") (class "Default")
      (node (ref "R17") (pin "2") (pinfunction "2_2") (pintype "passive"))
      (node (ref "U3") (pin "81") (pinfunction "81_81") (pintype "bidirectional"))
    )
    (net (code "71") (name "/SK") (class "Default")
      (node (ref "R2") (pin "1") (pinfunction "1_1") (pintype "passive"))
      (node (ref "U2") (pin "62") (pinfunction "EECLK_62") (pintype "bidirectional"))
      (node (ref "U6") (pin "2") (pinfunction "SK_2") (pintype "bidirectional"))
    )
    (net (code "72") (name "/TCK") (class "Default")
      (node (ref "U3") (pin "48") (pinfunction "TCK_48") (pintype "bidirectional"))
      (node (ref "U4") (pin "2") (pinfunction "B_2") (pintype "tri_state"))
    )
    (net (code "73") (name "/TCK1") (class "Default")
      (node (ref "R16") (pin "2") (pinfunction "2_2") (pintype "passive"))
      (node (ref "U3") (pin "91") (pinfunction "91_91") (pintype "bidirectional"))
    )
    (net (code "74") (name "/TDI") (class "Default")
      (node (ref "U3") (pin "45") (pinfunction "TDI_45") (pintype "bidirectional"))
      (node (ref "U4") (pin "3") (pinfunction "B_3") (pintype "tri_state"))
    )
    (net (code "75") (name "/TDI1") (class "Default")
      (node (ref "R14") (pin "2") (pinfunction "2_2") (pintype "passive"))
      (node (ref "U3") (pin "94") (pinfunction "94_94") (pintype "bidirectional"))
    )
    (net (code "76") (name "/TDO") (class "Default")
      (node (ref "U3") (pin "83") (pinfunction "TDO_83") (pintype "bidirectional"))
      (node (ref "U4") (pin "9") (pinfunction "B_9") (pintype "tri_state"))
    )
    (net (code "77") (name "/TDO1") (class "Default")
      (node (ref "R18") (pin "2") (pinfunction "2_2") (pintype "passive"))
      (node (ref "U3") (pin "79") (pinfunction "79_79") (pintype "bidirectional"))
    )
    (net (code "78") (name "/TMS") (class "Default")
      (node (ref "U3") (pin "47") (pinfunction "TMS_47") (pintype "bidirectional"))
      (node (ref "U4") (pin "10") (pinfunction "B_10") (pintype "tri_state"))
    )
    (net (code "79") (name "/TMS1") (class "Default")
      (node (ref "R15") (pin "2") (pinfunction "2_2") (pintype "passive"))
      (node (ref "U3") (pin "92") (pinfunction "92_92") (pintype "bidirectional"))
    )
    (net (code "80") (name "/TRST1") (class "Default")
      (node (ref "R3") (pin "2") (pinfunction "2_2") (pintype "passive"))
      (node (ref "U3") (pin "97") (pinfunction "97_97") (pintype "bidirectional"))
    )
    (net (code "81") (name "/TSRST1") (class "Default")
      (node (ref "R19") (pin "2") (pinfunction "2_2") (pintype "passive"))
      (node (ref "U3") (pin "78") (pinfunction "78_78") (pintype "bidirectional"))
    )
    (net (code "82") (name "/VT") (class "Default")
      (node (ref "C10") (pin "+") (pinfunction "C_EL+_+") (pintype "passive"))
      (node (ref "C19") (pin "1") (pinfunction "1_1") (pintype "passive"))
      (node (ref "C20") (pin "1") (pinfunction "1_1") (pintype "passive"))
      (node (ref "D4") (pin "C") (pinfunction "K_C") (pintype "passive"))
      (node (ref "R7") (pin "2") (pinfunction "2_2") (pintype "passive"))
      (node (ref "R8") (pin "2") (pinfunction "2_2") (pintype "passive"))
      (node (ref "U3") (pin "88") (pinfunction "VCCIO2_1_88") (pintype "bidirectional"))
      (node (ref "U3") (pin "98") (pinfunction "VCCIO2_2_98") (pintype "bidirectional"))
    )
    (net (code "83") (name "/VTG") (class "Default")
      (node (ref "R7") (pin "1") (pinfunction "1_1") (pintype "passive"))
      (node (ref "SV3") (pin "1") (pinfunction "K_1") (pintype "passive"))
      (node (ref "SV3") (pin "2") (pinfunction "K_2") (pintype "passive"))
      (node (ref "SV4") (pin "1") (pinfunction "K_1") (pintype "passive"))
      (node (ref "SV4") (pin "2") (pinfunction "K_2") (pintype "passive"))
      (node (ref "SV8") (pin "3") (pinfunction "K_3") (pintype "passive"))
      (node (ref "SV8") (pin "4") (pinfunction "K_4") (pintype "passive"))
    )
    (net (code "84") (name "GND") (class "Default")
      (node (ref "C1") (pin "1") (pinfunction "1_1") (pintype "passive"))
      (node (ref "C10") (pin "-") (pinfunction "C_EL-_-") (pintype "passive"))
      (node (ref "C11") (pin "1") (pinfunction "1_1") (pintype "passive"))
      (node (ref "C12") (pin "1") (pinfunction "1_1") (pintype "passive"))
      (node (ref "C13") (pin "1") (pinfunction "1_1") (pintype "passive"))
      (node (ref "C14") (pin "1") (pinfunction "1_1") (pintype "passive"))
      (node (ref "C15") (pin "1") (pinfunction "1_1") (pintype "passive"))
      (node (ref "C16") (pin "1") (pinfunction "1_1") (pintype "passive"))
      (node (ref "C17") (pin "1") (pinfunction "1_1") (pintype "passive"))
      (node (ref "C18") (pin "1") (pinfunction "1_1") (pintype "passive"))
      (node (ref "C19") (pin "2") (pinfunction "2_2") (pintype "passive"))
      (node (ref "C2") (pin "1") (pinfunction "1_1") (pintype "passive"))
      (node (ref "C20") (pin "2") (pinfunction "2_2") (pintype "passive"))
      (node (ref "C21") (pin "1") (pinfunction "1_1") (pintype "passive"))
      (node (ref "C22") (pin "-") (pinfunction "C_EL-_-") (pintype "passive"))
      (node (ref "C26") (pin "-") (pinfunction "C_EL-_-") (pintype "passive"))
      (node (ref "C27") (pin "-") (pinfunction "C_EL-_-") (pintype "passive"))
      (node (ref "C28") (pin "2") (pinfunction "2_2") (pintype "passive"))
      (node (ref "C29") (pin "2") (pinfunction "2_2") (pintype "passive"))
      (node (ref "C30") (pin "1") (pinfunction "1_1") (pintype "passive"))
      (node (ref "C31") (pin "1") (pinfunction "1_1") (pintype "passive"))
      (node (ref "C5") (pin "1") (pinfunction "1_1") (pintype "passive"))
      (node (ref "C6") (pin "1") (pinfunction "1_1") (pintype "passive"))
      (node (ref "C8") (pin "-") (pinfunction "C_EL-_-") (pintype "passive"))
      (node (ref "C9") (pin "1") (pinfunction "1_1") (pintype "passive"))
      (node (ref "D1") (pin "A") (pinfunction "A_A") (pintype "passive"))
      (node (ref "D2") (pin "K") (pinfunction "C_K") (pintype "passive"))
      (node (ref "D3") (pin "K") (pinfunction "C_K") (pintype "passive"))
      (node (ref "D4") (pin "A") (pinfunction "A_A") (pintype "passive"))
      (node (ref "R10") (pin "1") (pinfunction "1_1") (pintype "passive"))
      (node (ref "R4") (pin "1") (pinfunction "1_1") (pintype "passive"))
      (node (ref "R5") (pin "2") (pinfunction "2_2") (pintype "passive"))
      (node (ref "SV4") (pin "3") (pinfunction "K_3") (pintype "passive"))
      (node (ref "SV4") (pin "4") (pinfunction "K_4") (pintype "passive"))
      (node (ref "SV5") (pin "1") (pinfunction "K_1") (pintype "passive"))
      (node (ref "SV5") (pin "2") (pinfunction "K_2") (pintype "passive"))
      (node (ref "SV6") (pin "1") (pinfunction "K_1") (pintype "passive"))
      (node (ref "SV6") (pin "2") (pinfunction "K_2") (pintype "passive"))
      (node (ref "SV6") (pin "5") (pinfunction "K_5") (pintype "passive"))
      (node (ref "SV6") (pin "6") (pinfunction "K_6") (pintype "passive"))
      (node (ref "SV7") (pin "1") (pinfunction "K_1") (pintype "passive"))
      (node (ref "SV7") (pin "2") (pinfunction "K_2") (pintype "passive"))
      (node (ref "SV7") (pin "5") (pinfunction "K_5") (pintype "passive"))
      (node (ref "SV7") (pin "6") (pinfunction "K_6") (pintype "passive"))
      (node (ref "SV8") (pin "1") (pinfunction "K_1") (pintype "passive"))
      (node (ref "SV8") (pin "2") (pinfunction "K_2") (pintype "passive"))
      (node (ref "SV8") (pin "5") (pinfunction "K_5") (pintype "passive"))
      (node (ref "SV8") (pin "6") (pinfunction "K_6") (pintype "passive"))
      (node (ref "SW1") (pin "P$1") (pinfunction "P$1_P$1") (pintype "passive"))
      (node (ref "SW1") (pin "P$2") (pinfunction "P$1_P$2") (pintype "passive"))
      (node (ref "U1") (pin "1") (pinfunction "GND_1") (pintype "bidirectional"))
      (node (ref "U2") (pin "1") (pinfunction "GND0_1") (pintype "bidirectional"))
      (node (ref "U2") (pin "10") (pinfunction "AGND_10") (pintype "bidirectional"))
      (node (ref "U2") (pin "11") (pinfunction "GND2_11") (pintype "bidirectional"))
      (node (ref "U2") (pin "13") (pinfunction "TEST_13") (pintype "bidirectional"))
      (node (ref "U2") (pin "15") (pinfunction "GND3_15") (pintype "bidirectional"))
      (node (ref "U2") (pin "25") (pinfunction "GND4_25") (pintype "bidirectional"))
      (node (ref "U2") (pin "35") (pinfunction "GND5_35") (pintype "bidirectional"))
      (node (ref "U2") (pin "47") (pinfunction "GND6_47") (pintype "bidirectional"))
      (node (ref "U2") (pin "5") (pinfunction "GND1_5") (pintype "bidirectional"))
      (node (ref "U2") (pin "51") (pinfunction "GND7_51") (pintype "bidirectional"))
      (node (ref "U3") (pin "100") (pinfunction "GND6_100") (pintype "bidirectional"))
      (node (ref "U3") (pin "21") (pinfunction "GND1_21") (pintype "bidirectional"))
      (node (ref "U3") (pin "31") (pinfunction "GND2_31") (pintype "bidirectional"))
      (node (ref "U3") (pin "62") (pinfunction "GND3_62") (pintype "bidirectional"))
      (node (ref "U3") (pin "69") (pinfunction "GND4_69") (pintype "bidirectional"))
      (node (ref "U3") (pin "84") (pinfunction "GND5_84") (pintype "bidirectional"))
      (node (ref "U4") (pin "7") (pinfunction "VSS_7") (pintype "power_in"))
      (node (ref "U5") (pin "7") (pinfunction "VSS_7") (pintype "power_in"))
      (node (ref "U6") (pin "5") (pinfunction "GND_5") (pintype "bidirectional"))
      (node (ref "U6") (pin "7") (pinfunction "DC_7") (pintype "bidirectional"))
      (node (ref "X1") (pin "4") (pinfunction "GND_4") (pintype "bidirectional"))
      (node (ref "X1") (pin "GND") (pinfunction "GND_GND") (pintype "bidirectional"))
      (node (ref "X1") (pin "GND2") (pinfunction "GND_GND2") (pintype "bidirectional"))
      (node (ref "X2") (pin "P$1") (pinfunction "P$1_P$1") (pintype "bidirectional"))
      (node (ref "X3") (pin "P$1") (pinfunction "P$1_P$1") (pintype "bidirectional"))
      (node (ref "X4") (pin "P$1") (pinfunction "P$1_P$1") (pintype "bidirectional"))
      (node (ref "X5") (pin "P$1") (pinfunction "P$1_P$1") (pintype "bidirectional"))
    )
    (net (code "85") (name "Net-(C26-C_EL+)") (class "Default")
      (node (ref "C26") (pin "+") (pinfunction "C_EL+_+") (pintype "passive"))
      (node (ref "C30") (pin "2") (pinfunction "2_2") (pintype "passive"))
      (node (ref "L3") (pin "P$2") (pinfunction "2_P$2") (pintype "passive"))
      (node (ref "U2") (pin "9") (pinfunction "VPLL_9") (pintype "bidirectional"))
    )
    (net (code "86") (name "Net-(C27-C_EL+)") (class "Default")
      (node (ref "C27") (pin "+") (pinfunction "C_EL+_+") (pintype "passive"))
      (node (ref "C31") (pin "2") (pinfunction "2_2") (pintype "passive"))
      (node (ref "L4") (pin "P$2") (pinfunction "2_P$2") (pintype "passive"))
      (node (ref "U2") (pin "4") (pinfunction "VPHY_4") (pintype "bidirectional"))
    )
    (net (code "87") (name "Net-(D2-PadA)") (class "Default")
      (node (ref "D2") (pin "A") (pinfunction "A_A") (pintype "passive"))
      (node (ref "R11") (pin "1") (pinfunction "1_1") (pintype "passive"))
    )
    (net (code "88") (name "Net-(D3-PadA)") (class "Default")
      (node (ref "D3") (pin "A") (pinfunction "A_A") (pintype "passive"))
      (node (ref "R9") (pin "1") (pinfunction "1_1") (pintype "passive"))
    )
    (net (code "89") (name "Net-(L1-Pad1)") (class "Default")
      (node (ref "L1") (pin "1") (pinfunction "1_1") (pintype "passive"))
      (node (ref "P1") (pin "2") (pinfunction "2_2") (pintype "passive"))
    )
    (net (code "90") (name "Net-(R3-Pad1)") (class "Default")
      (node (ref "R3") (pin "1") (pinfunction "1_1") (pintype "passive"))
      (node (ref "SV3") (pin "3") (pinfunction "K_3") (pintype "passive"))
      (node (ref "SV3") (pin "4") (pinfunction "K_4") (pintype "passive"))
    )
    (net (code "91") (name "Net-(R14-Pad1)") (class "Default")
      (node (ref "R14") (pin "1") (pinfunction "1_1") (pintype "passive"))
      (node (ref "SV3") (pin "5") (pinfunction "K_5") (pintype "passive"))
      (node (ref "SV3") (pin "6") (pinfunction "K_6") (pintype "passive"))
    )
    (net (code "92") (name "Net-(R15-Pad1)") (class "Default")
      (node (ref "R15") (pin "1") (pinfunction "1_1") (pintype "passive"))
      (node (ref "SV3") (pin "7") (pinfunction "K_7") (pintype "passive"))
      (node (ref "SV3") (pin "8") (pinfunction "K_8") (pintype "passive"))
    )
    (net (code "93") (name "Net-(R16-Pad1)") (class "Default")
      (node (ref "R16") (pin "1") (pinfunction "1_1") (pintype "passive"))
      (node (ref "SV3") (pin "10") (pinfunction "K_10") (pintype "passive"))
      (node (ref "SV3") (pin "9") (pinfunction "K_9") (pintype "passive"))
    )
    (net (code "94") (name "Net-(R17-Pad1)") (class "Default")
      (node (ref "R17") (pin "1") (pinfunction "1_1") (pintype "passive"))
      (node (ref "SV3") (pin "11") (pinfunction "K_11") (pintype "passive"))
      (node (ref "SV3") (pin "12") (pinfunction "K_12") (pintype "passive"))
    )
    (net (code "95") (name "Net-(R18-Pad1)") (class "Default")
      (node (ref "R18") (pin "1") (pinfunction "1_1") (pintype "passive"))
      (node (ref "SV3") (pin "13") (pinfunction "K_13") (pintype "passive"))
      (node (ref "SV3") (pin "14") (pinfunction "K_14") (pintype "passive"))
    )
    (net (code "96") (name "Net-(R19-Pad1)") (class "Default")
      (node (ref "R19") (pin "1") (pinfunction "1_1") (pintype "passive"))
      (node (ref "SV3") (pin "15") (pinfunction "K_15") (pintype "passive"))
      (node (ref "SV3") (pin "16") (pinfunction "K_16") (pintype "passive"))
    )
    (net (code "97") (name "Net-(R20-Pad1)") (class "Default")
      (node (ref "R20") (pin "1") (pinfunction "1_1") (pintype "passive"))
      (node (ref "SV3") (pin "17") (pinfunction "K_17") (pintype "passive"))
      (node (ref "SV3") (pin "18") (pinfunction "K_18") (pintype "passive"))
    )
    (net (code "98") (name "Net-(R21-Pad1)") (class "Default")
      (node (ref "R21") (pin "1") (pinfunction "1_1") (pintype "passive"))
      (node (ref "SV3") (pin "19") (pinfunction "K_19") (pintype "passive"))
      (node (ref "SV3") (pin "20") (pinfunction "K_20") (pintype "passive"))
    )
    (net (code "99") (name "Net-(SV1A-P$1)") (class "Default")
      (node (ref "R5") (pin "1") (pinfunction "1_1") (pintype "passive"))
      (node (ref "SV1") (pin "1") (pinfunction "P$1_1") (pintype "passive"))
      (node (ref "U4") (pin "12") (pinfunction "C_12") (pintype "input"))
      (node (ref "U4") (pin "13") (pinfunction "C_13") (pintype "input"))
      (node (ref "U4") (pin "5") (pinfunction "C_5") (pintype "input"))
      (node (ref "U4") (pin "6") (pinfunction "C_6") (pintype "input"))
    )
    (net (code "100") (name "Net-(SV1C-P$1)") (class "Default")
      (node (ref "R4") (pin "2") (pinfunction "2_2") (pintype "passive"))
      (node (ref "SV1") (pin "3") (pinfunction "P$1_3") (pintype "passive"))
      (node (ref "U5") (pin "12") (pinfunction "C_12") (pintype "input"))
      (node (ref "U5") (pin "13") (pinfunction "C_13") (pintype "input"))
      (node (ref "U5") (pin "5") (pinfunction "C_5") (pintype "input"))
      (node (ref "U5") (pin "6") (pinfunction "C_6") (pintype "input"))
    )
    (net (code "101") (name "Net-(U2-OSC0)") (class "Default")
      (node (ref "C11") (pin "2") (pinfunction "2_2") (pintype "passive"))
      (node (ref "U2") (pin "3") (pinfunction "OSC0_3") (pintype "bidirectional"))
      (node (ref "XTAL1") (pin "P$2") (pinfunction "2_P$2") (pintype "passive"))
    )
    (net (code "102") (name "Net-(U2-OSCI)") (class "Default")
      (node (ref "C12") (pin "2") (pinfunction "2_2") (pintype "passive"))
      (node (ref "U2") (pin "2") (pinfunction "OSCI_2") (pintype "bidirectional"))
      (node (ref "XTAL1") (pin "P$1") (pinfunction "1_P$1") (pintype "passive"))
    )
    (net (code "103") (name "Net-(U2-REF)") (class "Default")
      (node (ref "R10") (pin "2") (pinfunction "2_2") (pintype "passive"))
      (node (ref "U2") (pin "6") (pinfunction "REF_6") (pintype "bidirectional"))
    )
    (net (code "104") (name "Net-(U2-RESET#)") (class "Default")
      (node (ref "R12") (pin "2") (pinfunction "2_2") (pintype "passive"))
      (node (ref "U2") (pin "14") (pinfunction "RESET#_14") (pintype "bidirectional"))
    )
    (net (code "105") (name "Net-(U2-VREGOUT)") (class "Default")
      (node (ref "R22") (pin "1") (pinfunction "1_1") (pintype "passive"))
      (node (ref "U2") (pin "49") (pinfunction "VREGOUT_49") (pintype "bidirectional"))
    )
    (net (code "106") (name "Net-(X1-+5V)") (class "Default")
      (node (ref "P1") (pin "1") (pinfunction "1_1") (pintype "passive"))
      (node (ref "X1") (pin "1") (pinfunction "+5V_1") (pintype "bidirectional"))
    )
    (net (code "107") (name "unconnected-(U2-PWREN#-Pad60)") (class "Default")
      (node (ref "U2") (pin "60") (pinfunction "PWREN#_60") (pintype "bidirectional"))
    )
    (net (code "108") (name "unconnected-(U2-SUSPEND#-Pad36)") (class "Default")
      (node (ref "U2") (pin "36") (pinfunction "SUSPEND#_36") (pintype "bidirectional"))
    )
    (net (code "109") (name "unconnected-(U3-NC1-Pad20)") (class "Default")
      (node (ref "U3") (pin "20") (pinfunction "NC1_20") (pintype "bidirectional"))
    )
    (net (code "110") (name "unconnected-(U3-NC2-Pad25)") (class "Default")
      (node (ref "U3") (pin "25") (pinfunction "NC2_25") (pintype "bidirectional"))
    )
    (net (code "111") (name "unconnected-(U3-NC3-Pad44)") (class "Default")
      (node (ref "U3") (pin "44") (pinfunction "NC3_44") (pintype "bidirectional"))
    )
    (net (code "112") (name "unconnected-(U3-NC4-Pad46)") (class "Default")
      (node (ref "U3") (pin "46") (pinfunction "NC4_46") (pintype "bidirectional"))
    )
    (net (code "113") (name "unconnected-(U3-NC5-Pad54)") (class "Default")
      (node (ref "U3") (pin "54") (pinfunction "NC5_54") (pintype "bidirectional"))
    )
    (net (code "114") (name "unconnected-(U3-NC6-Pad59)") (class "Default")
      (node (ref "U3") (pin "59") (pinfunction "NC6_59") (pintype "bidirectional"))
    )
    (net (code "115") (name "unconnected-(U3-NC7-Pad63)") (class "Default")
      (node (ref "U3") (pin "63") (pinfunction "NC7_63") (pintype "bidirectional"))
    )
    (net (code "116") (name "unconnected-(U3-NC8-Pad65)") (class "Default")
      (node (ref "U3") (pin "65") (pinfunction "NC8_65") (pintype "bidirectional"))
    )
    (net (code "117") (name "unconnected-(U3-NC9-Pad66)") (class "Default")
      (node (ref "U3") (pin "66") (pinfunction "NC9_66") (pintype "bidirectional"))
    )
    (net (code "118") (name "unconnected-(U3-NC10-Pad73)") (class "Default")
      (node (ref "U3") (pin "73") (pinfunction "NC10_73") (pintype "bidirectional"))
    )
    (net (code "119") (name "unconnected-(U3-NC11-Pad75)") (class "Default")
      (node (ref "U3") (pin "75") (pinfunction "NC11_75") (pintype "bidirectional"))
    )
    (net (code "120") (name "unconnected-(U3-NC12-Pad80)") (class "Default")
      (node (ref "U3") (pin "80") (pinfunction "NC12_80") (pintype "bidirectional"))
    )
    (net (code "121") (name "unconnected-(U3-NC13-Pad82)") (class "Default")
      (node (ref "U3") (pin "82") (pinfunction "NC13_82") (pintype "bidirectional"))
    )
    (net (code "122") (name "unconnected-(U3-NC14-Pad85)") (class "Default")
      (node (ref "U3") (pin "85") (pinfunction "NC14_85") (pintype "bidirectional"))
    )
    (net (code "123") (name "unconnected-(U3-NC15-Pad86)") (class "Default")
      (node (ref "U3") (pin "86") (pinfunction "NC15_86") (pintype "bidirectional"))
    )
    (net (code "124") (name "unconnected-(U3-NC16-Pad87)") (class "Default")
      (node (ref "U3") (pin "87") (pinfunction "NC16_87") (pintype "bidirectional"))
    )
    (net (code "125") (name "unconnected-(U3-NC17-Pad93)") (class "Default")
      (node (ref "U3") (pin "93") (pinfunction "NC17_93") (pintype "bidirectional"))
    )
    (net (code "126") (name "unconnected-(U3-NC18-Pad95)") (class "Default")
      (node (ref "U3") (pin "95") (pinfunction "NC18_95") (pintype "bidirectional"))
    )
    (net (code "127") (name "unconnected-(U3-NC19-Pad96)") (class "Default")
      (node (ref "U3") (pin "96") (pinfunction "NC19_96") (pintype "bidirectional"))
    )
  )
)
